# Platine_2.net
KiCad netlist of a schematic drawn in EAGLE
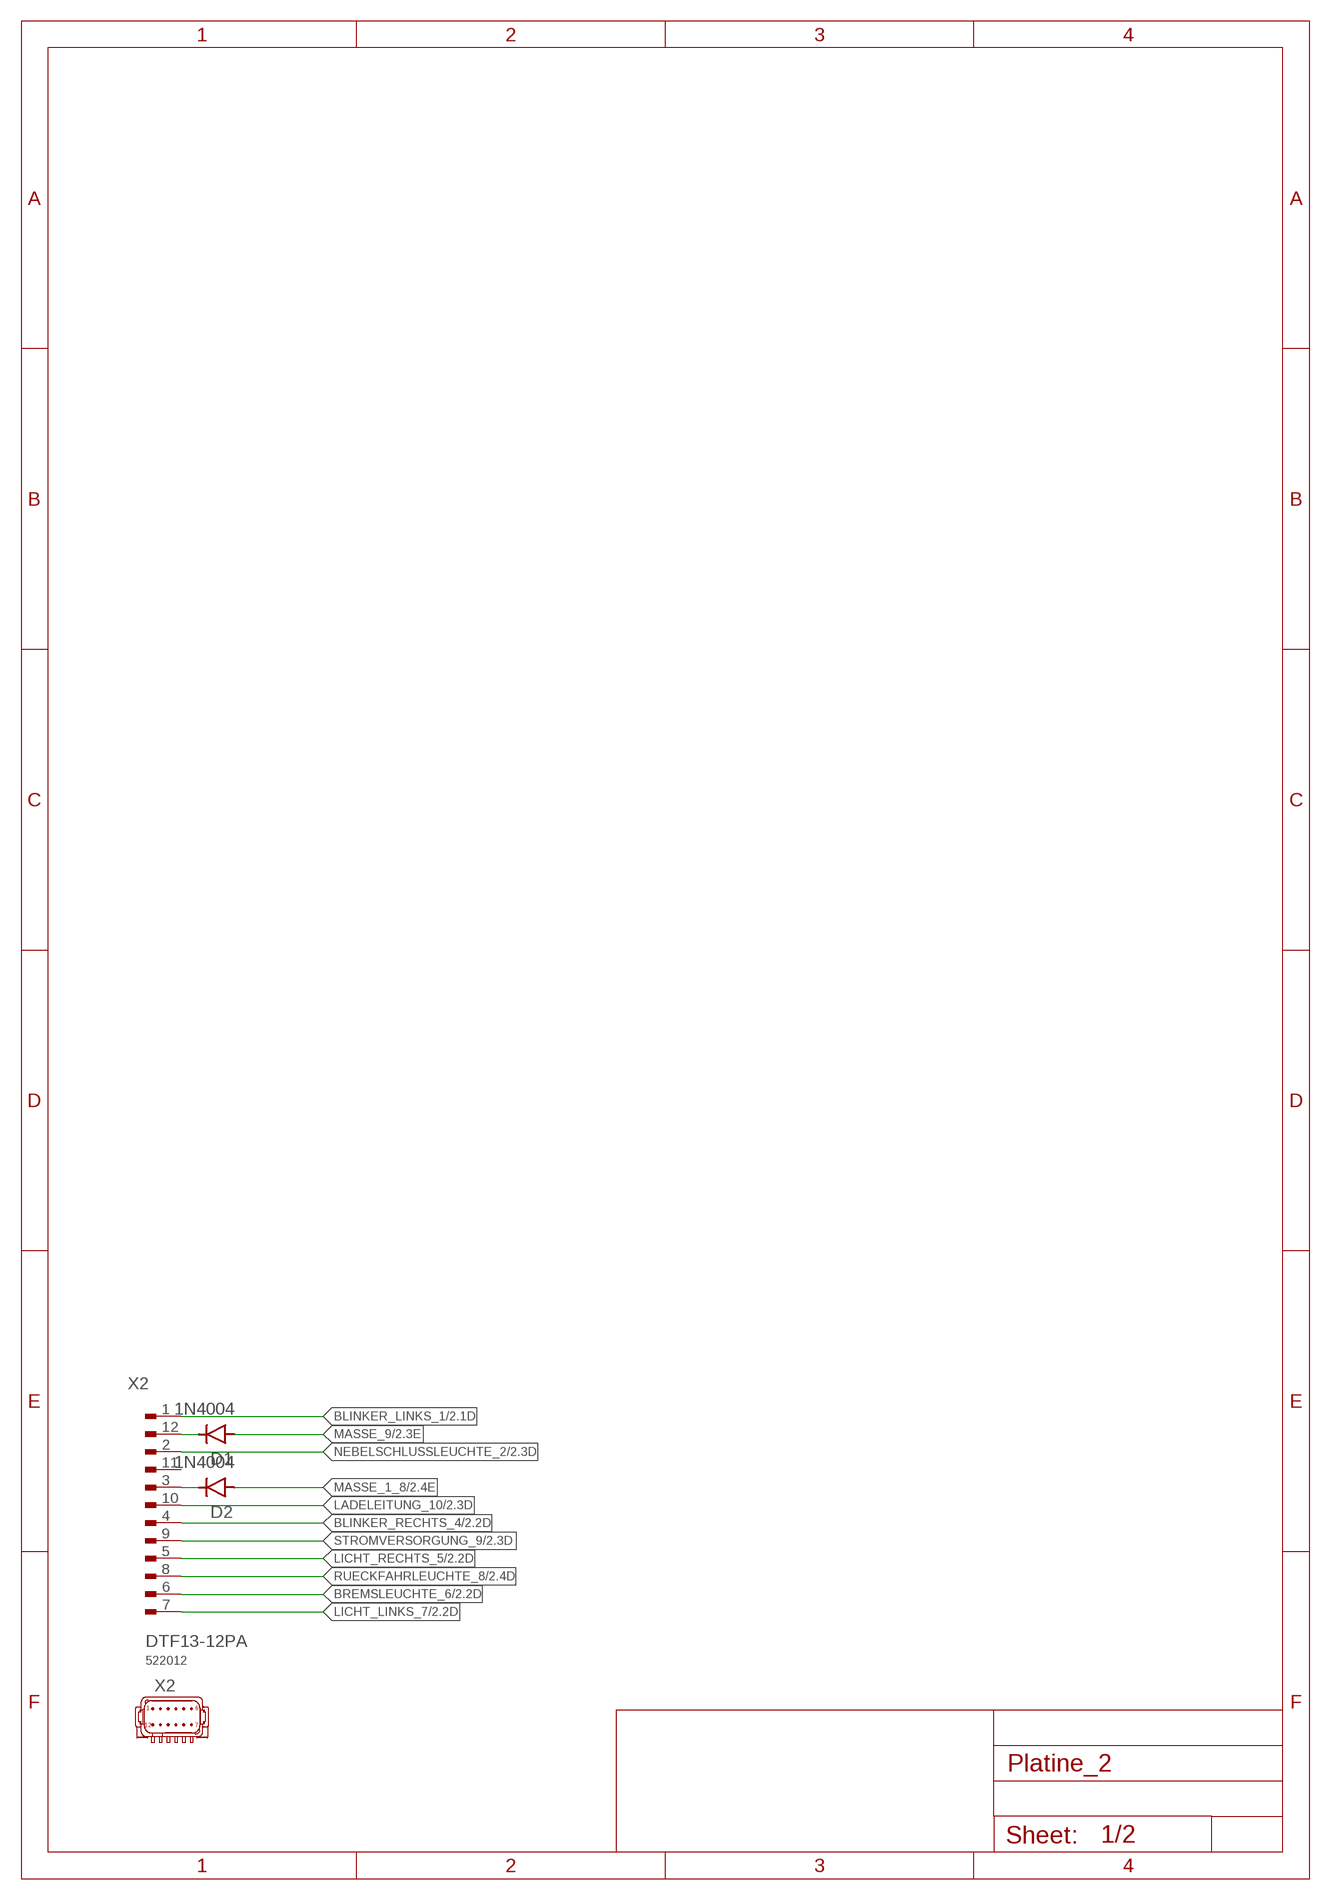
[diagram p0: schematic, sheet 1]
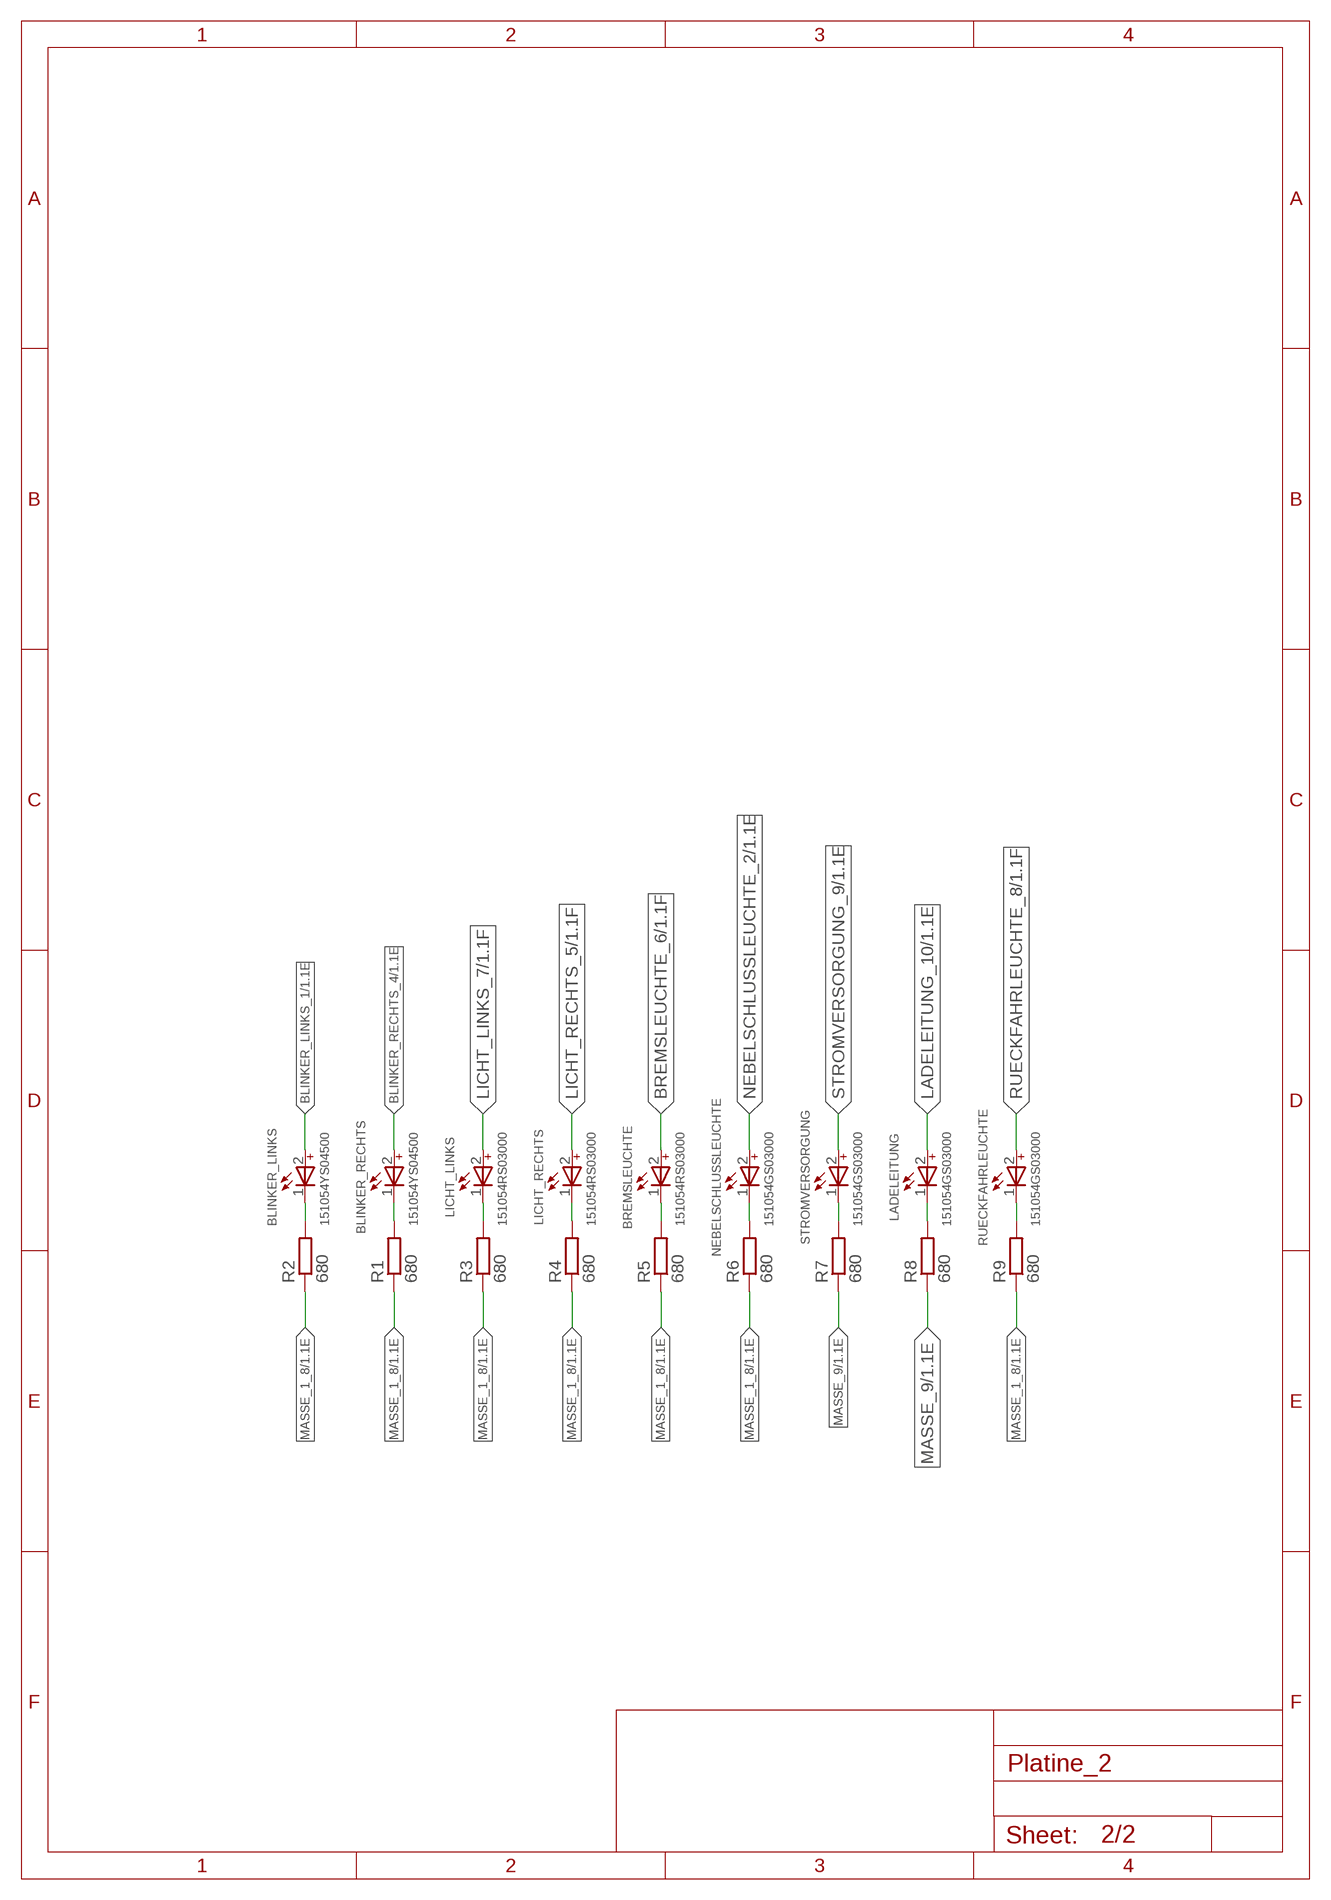
[diagram p1: schematic, sheet 2]

(export (version "E")
  (design (tool "Eeschema 10.0.6"))
  (components
    (comp (ref "BLINKER_LINKS")
      (value "151054YS04500")
      (footprint "eagle-import:WL-TMRW_5MM")
      (libsource (lib "eagle-import") (part "WL-TMRW_5MM_WITHOUTSTOPPER_151054YS04500"))
    )
    (comp (ref "BLINKER_RECHTS")
      (value "151054YS04500")
      (footprint "eagle-import:WL-TMRW_5MM")
      (libsource (lib "eagle-import") (part "WL-TMRW_5MM_WITHOUTSTOPPER_151054YS04500"))
    )
    (comp (ref "BREMSLEUCHTE")
      (value "151054RS03000")
      (footprint "eagle-import:WL-TMRW_5MM")
      (libsource (lib "eagle-import") (part "WL-TMRW_5MM_WITHOUTSTOPPER_151054RS03000"))
    )
    (comp (ref "LADELEITUNG")
      (value "151054GS03000")
      (footprint "eagle-import:WL-TMRW_5MM")
      (libsource (lib "eagle-import") (part "WL-TMRW_5MM_WITHOUTSTOPPER_151054GS03000"))
    )
    (comp (ref "LICHT_LINKS")
      (value "151054RS03000")
      (footprint "eagle-import:WL-TMRW_5MM")
      (libsource (lib "eagle-import") (part "WL-TMRW_5MM_WITHOUTSTOPPER_151054RS03000"))
    )
    (comp (ref "LICHT_RECHTS")
      (value "151054RS03000")
      (footprint "eagle-import:WL-TMRW_5MM")
      (libsource (lib "eagle-import") (part "WL-TMRW_5MM_WITHOUTSTOPPER_151054RS03000"))
    )
    (comp (ref "NEBELSCHLUSSLEUCHTE")
      (value "151054GS03000")
      (footprint "eagle-import:WL-TMRW_5MM")
      (libsource (lib "eagle-import") (part "WL-TMRW_5MM_WITHOUTSTOPPER_151054GS03000"))
    )
    (comp (ref "R1")
      (value "680")
      (footprint "eagle-import:0204_7")
      (libsource (lib "eagle-import") (part "R-EU_0204/7"))
    )
    (comp (ref "R2")
      (value "680")
      (footprint "eagle-import:0204_7")
      (libsource (lib "eagle-import") (part "R-EU_0204/7"))
    )
    (comp (ref "R3")
      (value "680")
      (footprint "eagle-import:0204_7")
      (libsource (lib "eagle-import") (part "R-EU_0204/7"))
    )
    (comp (ref "R4")
      (value "680")
      (footprint "eagle-import:0204_7")
      (libsource (lib "eagle-import") (part "R-EU_0204/7"))
    )
    (comp (ref "R5")
      (value "680")
      (footprint "eagle-import:0204_7")
      (libsource (lib "eagle-import") (part "R-EU_0204/7"))
    )
    (comp (ref "R6")
      (value "680")
      (footprint "eagle-import:0204_7")
      (libsource (lib "eagle-import") (part "R-EU_0204/7"))
    )
    (comp (ref "R7")
      (value "680")
      (footprint "eagle-import:0204_7")
      (libsource (lib "eagle-import") (part "R-EU_0204/7"))
    )
    (comp (ref "R8")
      (value "680")
      (footprint "eagle-import:0204_7")
      (libsource (lib "eagle-import") (part "R-EU_0204/7"))
    )
    (comp (ref "R9")
      (value "680")
      (footprint "eagle-import:0204_7")
      (libsource (lib "eagle-import") (part "R-EU_0204/7"))
    )
    (comp (ref "RUECKFAHRLEUCHTE")
      (value "151054GS03000")
      (footprint "eagle-import:WL-TMRW_5MM")
      (libsource (lib "eagle-import") (part "WL-TMRW_5MM_WITHOUTSTOPPER_151054GS03000"))
    )
    (comp (ref "STROMVERSORGUNG")
      (value "151054GS03000")
      (footprint "eagle-import:WL-TMRW_5MM")
      (libsource (lib "eagle-import") (part "WL-TMRW_5MM_WITHOUTSTOPPER_151054GS03000"))
    )
    (comp (ref "D1")
      (value "1N4004")
      (footprint "eagle-import:DO-41")
      (fields
        (field (name "DIGIKEY_PART_NUMBER") "1N4004MSCT-ND")
        (field (name "MANUFACTURER") "Micro Commercial Co")
        (field (name "CREATED_BY") "PCBLayout.com")
      )
      (libsource (lib "eagle-import") (part "1N4004"))
    )
    (comp (ref "D2")
      (value "1N4004")
      (footprint "eagle-import:DO-41")
      (fields
        (field (name "DIGIKEY_PART_NUMBER") "1N4004MSCT-ND")
        (field (name "MANUFACTURER") "Micro Commercial Co")
        (field (name "CREATED_BY") "PCBLayout.com")
      )
      (libsource (lib "eagle-import") (part "1N4004"))
    )
    (comp (ref "X2")
      (value "DTF13-12PA")
      (footprint "eagle-import:DTF13-12PA")
      (fields (field (name "ARTIKEL_NR") "522012"))
      (libsource (lib "eagle-import") (part "DTF13-12PA"))
    )
  )
  (nets
    (net (code "1") (name "BLINKER_LINKS_1") (class "Default")
      (node (ref "BLINKER_LINKS") (pin "2") (pinfunction "+_2") (pintype "passive"))
      (node (ref "X2") (pin "1") (pinfunction "1_1") (pintype "passive"))
    )
    (net (code "2") (name "BLINKER_RECHTS_4") (class "Default")
      (node (ref "BLINKER_RECHTS") (pin "2") (pinfunction "+_2") (pintype "passive"))
      (node (ref "X2") (pin "4") (pinfunction "4_4") (pintype "passive"))
    )
    (net (code "3") (name "BREMSLEUCHTE_6") (class "Default")
      (node (ref "BREMSLEUCHTE") (pin "2") (pinfunction "+_2") (pintype "passive"))
      (node (ref "X2") (pin "6") (pinfunction "6_6") (pintype "passive"))
    )
    (net (code "4") (name "LADELEITUNG_10") (class "Default")
      (node (ref "LADELEITUNG") (pin "2") (pinfunction "+_2") (pintype "passive"))
      (node (ref "X2") (pin "10") (pinfunction "10_10") (pintype "passive"))
    )
    (net (code "5") (name "LICHT_LINKS_7") (class "Default")
      (node (ref "LICHT_LINKS") (pin "2") (pinfunction "+_2") (pintype "passive"))
      (node (ref "X2") (pin "7") (pinfunction "7_7") (pintype "passive"))
    )
    (net (code "6") (name "LICHT_RECHTS_5") (class "Default")
      (node (ref "LICHT_RECHTS") (pin "2") (pinfunction "+_2") (pintype "passive"))
      (node (ref "X2") (pin "5") (pinfunction "5_5") (pintype "passive"))
    )
    (net (code "7") (name "MASSE_1_8") (class "Default")
      (node (ref "D2") (pin "A") (pinfunction "A_A") (pintype "passive"))
      (node (ref "R1") (pin "1") (pinfunction "1_1") (pintype "passive"))
      (node (ref "R2") (pin "1") (pinfunction "1_1") (pintype "passive"))
      (node (ref "R3") (pin "1") (pinfunction "1_1") (pintype "passive"))
      (node (ref "R4") (pin "1") (pinfunction "1_1") (pintype "passive"))
      (node (ref "R5") (pin "1") (pinfunction "1_1") (pintype "passive"))
      (node (ref "R6") (pin "1") (pinfunction "1_1") (pintype "passive"))
      (node (ref "R9") (pin "1") (pinfunction "1_1") (pintype "passive"))
    )
    (net (code "8") (name "MASSE_9") (class "Default")
      (node (ref "D1") (pin "A") (pinfunction "A_A") (pintype "passive"))
      (node (ref "R7") (pin "1") (pinfunction "1_1") (pintype "passive"))
      (node (ref "R8") (pin "1") (pinfunction "1_1") (pintype "passive"))
    )
    (net (code "9") (name "NEBELSCHLUSSLEUCHTE_2") (class "Default")
      (node (ref "NEBELSCHLUSSLEUCHTE") (pin "2") (pinfunction "+_2") (pintype "passive"))
      (node (ref "X2") (pin "2") (pinfunction "2_2") (pintype "passive"))
    )
    (net (code "10") (name "Net-(BLINKER_LINKS--)") (class "Default")
      (node (ref "BLINKER_LINKS") (pin "1") (pinfunction "-_1") (pintype "passive"))
      (node (ref "R2") (pin "2") (pinfunction "2_2") (pintype "passive"))
    )
    (net (code "11") (name "Net-(BLINKER_RECHTS--)") (class "Default")
      (node (ref "BLINKER_RECHTS") (pin "1") (pinfunction "-_1") (pintype "passive"))
      (node (ref "R1") (pin "2") (pinfunction "2_2") (pintype "passive"))
    )
    (net (code "12") (name "Net-(BREMSLEUCHTE--)") (class "Default")
      (node (ref "BREMSLEUCHTE") (pin "1") (pinfunction "-_1") (pintype "passive"))
      (node (ref "R5") (pin "2") (pinfunction "2_2") (pintype "passive"))
    )
    (net (code "13") (name "Net-(D1-PadC)") (class "Default")
      (node (ref "D1") (pin "C") (pinfunction "C_C") (pintype "passive"))
      (node (ref "X2") (pin "12") (pinfunction "12_12") (pintype "passive"))
    )
    (net (code "14") (name "Net-(D2-PadC)") (class "Default")
      (node (ref "D2") (pin "C") (pinfunction "C_C") (pintype "passive"))
      (node (ref "X2") (pin "3") (pinfunction "3_3") (pintype "passive"))
    )
    (net (code "15") (name "Net-(LADELEITUNG--)") (class "Default")
      (node (ref "LADELEITUNG") (pin "1") (pinfunction "-_1") (pintype "passive"))
      (node (ref "R8") (pin "2") (pinfunction "2_2") (pintype "passive"))
    )
    (net (code "16") (name "Net-(LICHT_LINKS--)") (class "Default")
      (node (ref "LICHT_LINKS") (pin "1") (pinfunction "-_1") (pintype "passive"))
      (node (ref "R3") (pin "2") (pinfunction "2_2") (pintype "passive"))
    )
    (net (code "17") (name "Net-(LICHT_RECHTS--)") (class "Default")
      (node (ref "LICHT_RECHTS") (pin "1") (pinfunction "-_1") (pintype "passive"))
      (node (ref "R4") (pin "2") (pinfunction "2_2") (pintype "passive"))
    )
    (net (code "18") (name "Net-(NEBELSCHLUSSLEUCHTE--)") (class "Default")
      (node (ref "NEBELSCHLUSSLEUCHTE") (pin "1") (pinfunction "-_1") (pintype "passive"))
      (node (ref "R6") (pin "2") (pinfunction "2_2") (pintype "passive"))
    )
    (net (code "19") (name "Net-(RUECKFAHRLEUCHTE--)") (class "Default")
      (node (ref "R9") (pin "2") (pinfunction "2_2") (pintype "passive"))
      (node (ref "RUECKFAHRLEUCHTE") (pin "1") (pinfunction "-_1") (pintype "passive"))
    )
    (net (code "20") (name "Net-(STROMVERSORGUNG--)") (class "Default")
      (node (ref "R7") (pin "2") (pinfunction "2_2") (pintype "passive"))
      (node (ref "STROMVERSORGUNG") (pin "1") (pinfunction "-_1") (pintype "passive"))
    )
    (net (code "21") (name "RUECKFAHRLEUCHTE_8") (class "Default")
      (node (ref "RUECKFAHRLEUCHTE") (pin "2") (pinfunction "+_2") (pintype "passive"))
      (node (ref "X2") (pin "8") (pinfunction "8_8") (pintype "passive"))
    )
    (net (code "22") (name "STROMVERSORGUNG_9") (class "Default")
      (node (ref "STROMVERSORGUNG") (pin "2") (pinfunction "+_2") (pintype "passive"))
      (node (ref "X2") (pin "9") (pinfunction "9_9") (pintype "passive"))
    )
    (net (code "23") (name "unconnected-(X2-Pad11)") (class "Default")
      (node (ref "X2") (pin "11") (pinfunction "11_11") (pintype "passive"))
    )
  )
)
